# PressureandTemperature.net
KiCad netlist of a schematic drawn in Altium Designer
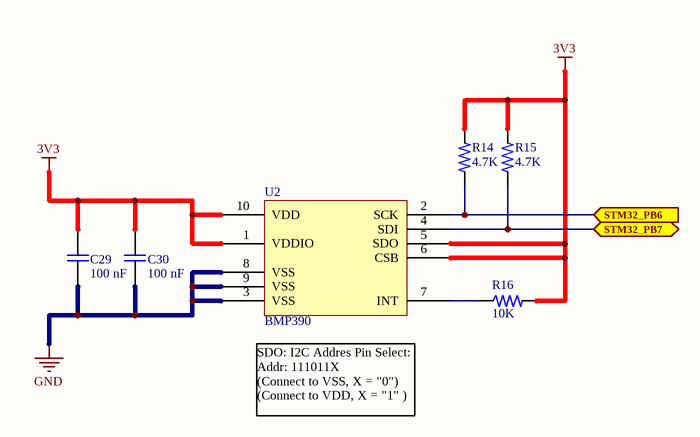
[diagram p0: PressureandTemperature.SchDoc]

(export (version "E")
  (design (tool "Eeschema 10.0.6"))
  (components
    (comp (ref "C29")
      (value "100 nF")
      (footprint "MergenElektronik_Capacitors_Ceramics_SMDs_0603_M_NS")
      (description "Mergen Elektronik - Capacitors - Ceramics - SMDs - 0603 - 100 nF - 100V")
      (fields (field (name "MANUFACTURER") "Samsung Electro-Mechanics") (field (name "TOLERANCE") "±10%"))
      (libsource (lib "MergenElektronik_Capacitors_Ceramics_SMDs") (part "MergenElektronik_Capacitors_Ceramic_SMDs_100nF_100V"))
    )
    (comp (ref "C30")
      (value "100 nF")
      (footprint "MergenElektronik_Capacitors_Ceramics_SMDs_0603_M_NS")
      (description "Mergen Elektronik - Capacitors - Ceramics - SMDs - 0603 - 100 nF - 100V")
      (fields (field (name "MANUFACTURER") "Samsung Electro-Mechanics") (field (name "TOLERANCE") "±10%"))
      (libsource (lib "MergenElektronik_Capacitors_Ceramics_SMDs") (part "MergenElektronik_Capacitors_Ceramic_SMDs_100nF_100V"))
    )
    (comp (ref "R14")
      (value "4.7K")
      (footprint "MergenElektronik_Resistors_ChipResistors_0603_M_NS")
      (description "Mergen Elektronik - Resistors - Chip Resistors - 0603 - 4.7K")
      (fields (field (name "MANUFACTURER") "Stackpole Electronics Inc") (field (name "POWER") "1/10W"))
      (libsource (lib "MergenElektronik_Resistors_ChipResistors") (part "MergenElektronik_Resistors_ChipResistors_0603_4.7K"))
    )
    (comp (ref "R15")
      (value "4.7K")
      (footprint "MergenElektronik_Resistors_ChipResistors_0603_M_NS")
      (description "Mergen Elektronik - Resistors - Chip Resistors - 0603 - 4.7K")
      (fields (field (name "MANUFACTURER") "Stackpole Electronics Inc") (field (name "POWER") "1/10W"))
      (libsource (lib "MergenElektronik_Resistors_ChipResistors") (part "MergenElektronik_Resistors_ChipResistors_0603_4.7K"))
    )
    (comp (ref "R16")
      (value "10K")
      (footprint "MergenElektronik_Resistors_ChipResistors_0603_M_NS")
      (description "Mergen Elektronik - Resistors - Chip Resistors - 0603 - 10K")
      (fields (field (name "MANUFACTURER") "Stackpole Electronics Inc") (field (name "POWER") "1/10W"))
      (libsource (lib "MergenElektronik_Resistors_ChipResistors") (part "MergenElektronik_Resistors_ChipResistors_0603_10K"))
    )
    (comp (ref "U2")
      (value "BMP390")
      (footprint "MergenElektronik_Sensors_PressureSensors_10-WFLGA")
      (description "Mergen Elektronik - Sensors - Pressure Sensors - BMP390")
      (fields (field (name "MANUFACTURER") "Bosch Sensortec") (field (name "TOLERANCE") "±0.01PSI (0.05kPa)"))
      (libsource (lib "MergenElektronik_Sensors_PressureSensors") (part "MergenElektronik_Sensors_PressureSensors_BMP390"))
    )
  )
  (nets
    (net (code "1") (name "/STM32_PB6") (class "Default")
      (node (ref "R14") (pin "1") (pinfunction "1_1") (pintype "passive"))
      (node (ref "U2") (pin "2") (pinfunction "SCK_2") (pintype "passive"))
    )
    (net (code "2") (name "/STM32_PB7") (class "Default")
      (node (ref "R15") (pin "1") (pinfunction "1_1") (pintype "passive"))
      (node (ref "U2") (pin "4") (pinfunction "SDI_4") (pintype "passive"))
    )
    (net (code "3") (name "3V3") (class "Default")
      (node (ref "C29") (pin "1") (pinfunction "1_1") (pintype "passive"))
      (node (ref "C30") (pin "1") (pinfunction "1_1") (pintype "passive"))
      (node (ref "R14") (pin "2") (pinfunction "2_2") (pintype "passive"))
      (node (ref "R15") (pin "2") (pinfunction "2_2") (pintype "passive"))
      (node (ref "R16") (pin "2") (pinfunction "2_2") (pintype "passive"))
      (node (ref "U2") (pin "1") (pinfunction "VDDIO_1") (pintype "passive"))
      (node (ref "U2") (pin "10") (pinfunction "VDD_10") (pintype "passive"))
      (node (ref "U2") (pin "5") (pinfunction "SDO_5") (pintype "passive"))
      (node (ref "U2") (pin "6") (pinfunction "CSB_6") (pintype "passive"))
    )
    (net (code "4") (name "GND") (class "Default")
      (node (ref "C29") (pin "2") (pinfunction "2_2") (pintype "passive"))
      (node (ref "C30") (pin "2") (pinfunction "2_2") (pintype "passive"))
      (node (ref "U2") (pin "3") (pinfunction "VSS_3") (pintype "passive"))
      (node (ref "U2") (pin "8") (pinfunction "VSS_8") (pintype "passive"))
      (node (ref "U2") (pin "9") (pinfunction "VSS_9") (pintype "passive"))
    )
    (net (code "5") (name "Net-(U2-INT)") (class "Default")
      (node (ref "R16") (pin "1") (pinfunction "1_1") (pintype "passive"))
      (node (ref "U2") (pin "7") (pinfunction "INT_7") (pintype "passive"))
    )
  )
)
